# cs4272-breakout-board.net
KiCad netlist of a schematic drawn in EAGLE
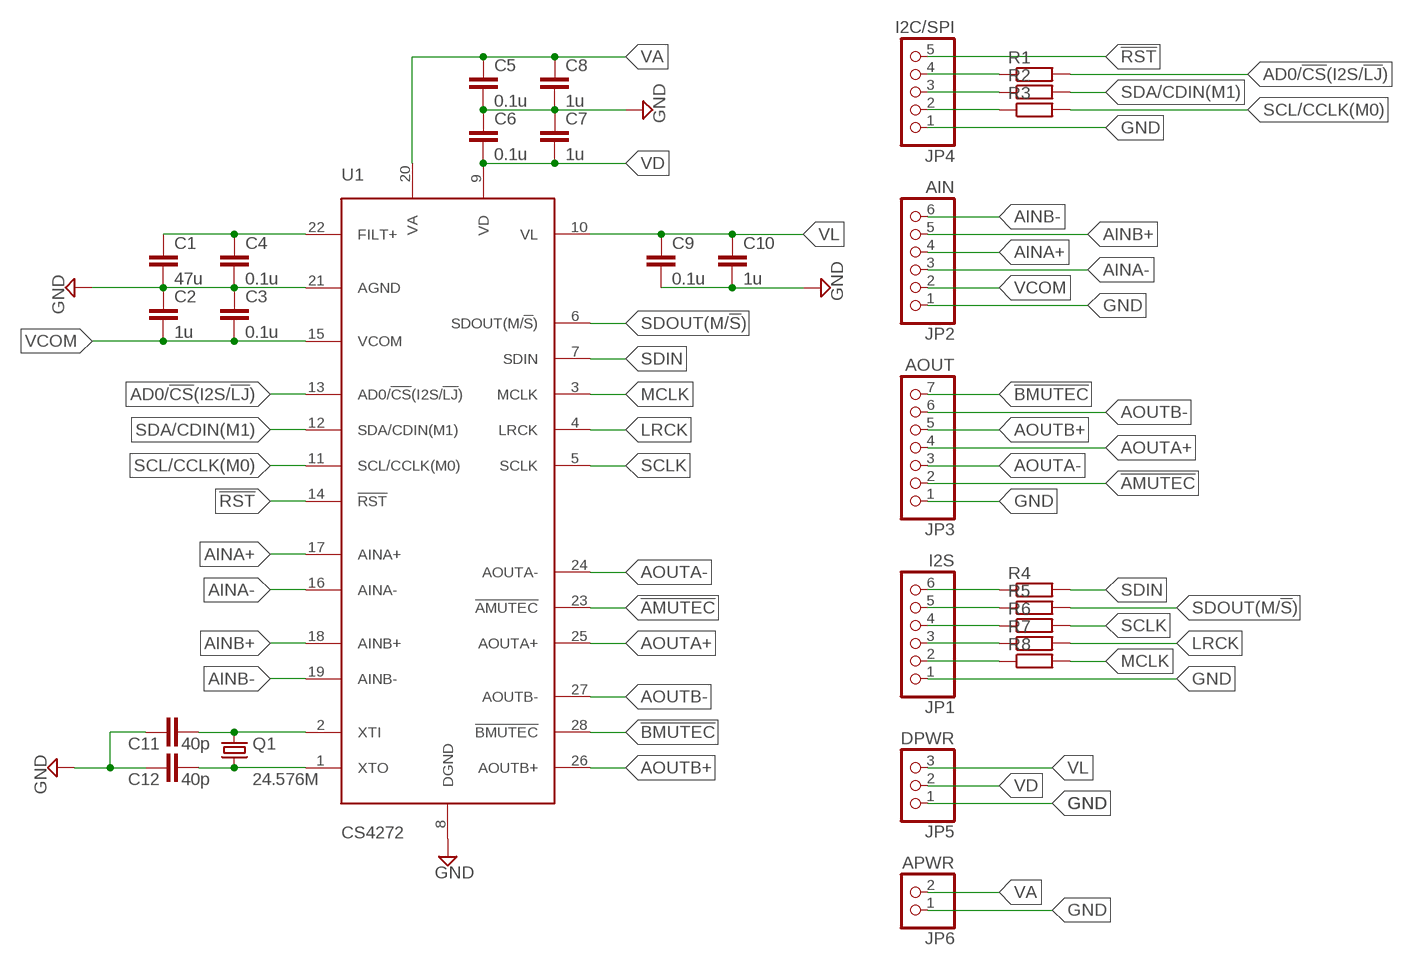
[diagram p0: schematic, sheet 1]

(export (version "E")
  (design (tool "Eeschema 10.0.6"))
  (components
    (comp (ref "C1")
      (value "47u")
      (footprint "eagle-import:C0603")
      (libsource (lib "eagle-import") (part "C-EUC0603"))
    )
    (comp (ref "C2")
      (value "1u")
      (footprint "eagle-import:C0603")
      (libsource (lib "eagle-import") (part "C-EUC0603"))
    )
    (comp (ref "C3")
      (value "0.1u")
      (footprint "eagle-import:C0603")
      (libsource (lib "eagle-import") (part "C-EUC0603"))
    )
    (comp (ref "C4")
      (value "0.1u")
      (footprint "eagle-import:C0603")
      (libsource (lib "eagle-import") (part "C-EUC0603"))
    )
    (comp (ref "C5")
      (value "0.1u")
      (footprint "eagle-import:C0603")
      (libsource (lib "eagle-import") (part "C-EUC0603"))
    )
    (comp (ref "C6")
      (value "0.1u")
      (footprint "eagle-import:C0603")
      (libsource (lib "eagle-import") (part "C-EUC0603"))
    )
    (comp (ref "C7")
      (value "1u")
      (footprint "eagle-import:C0603")
      (libsource (lib "eagle-import") (part "C-EUC0603"))
    )
    (comp (ref "C8")
      (value "1u")
      (footprint "eagle-import:C0603")
      (libsource (lib "eagle-import") (part "C-EUC0603"))
    )
    (comp (ref "C9")
      (value "0.1u")
      (footprint "eagle-import:C0603")
      (libsource (lib "eagle-import") (part "C-EUC0603"))
    )
    (comp (ref "C10")
      (value "1u")
      (footprint "eagle-import:C0603")
      (libsource (lib "eagle-import") (part "C-EUC0603"))
    )
    (comp (ref "C11")
      (value "40p")
      (footprint "eagle-import:C0603")
      (libsource (lib "eagle-import") (part "C-EUC0603"))
    )
    (comp (ref "C12")
      (value "40p")
      (footprint "eagle-import:C0603")
      (libsource (lib "eagle-import") (part "C-EUC0603"))
    )
    (comp (ref "JP1")
      (value "I2S")
      (footprint "eagle-import:1X06")
      (libsource (lib "eagle-import") (part "PINHD-1X6"))
    )
    (comp (ref "JP2")
      (value "AIN")
      (footprint "eagle-import:1X06")
      (libsource (lib "eagle-import") (part "PINHD-1X6"))
    )
    (comp (ref "JP3")
      (value "AOUT")
      (footprint "eagle-import:1X07")
      (libsource (lib "eagle-import") (part "PINHD-1X7"))
    )
    (comp (ref "JP4")
      (value "I2C/SPI")
      (footprint "eagle-import:1X05")
      (libsource (lib "eagle-import") (part "PINHD-1X5"))
    )
    (comp (ref "JP5")
      (value "DPWR")
      (footprint "eagle-import:1X03")
      (libsource (lib "eagle-import") (part "PINHD-1X3"))
    )
    (comp (ref "JP6")
      (value "APWR")
      (footprint "eagle-import:1X02")
      (libsource (lib "eagle-import") (part "PINHD-1X2"))
    )
    (comp (ref "Q1")
      (value "24.576M")
      (footprint "eagle-import:HC49_S")
      (libsource (lib "eagle-import") (part "CRYSTALHC49S"))
    )
    (comp (ref "R1")
      (value "R-EU_R0603")
      (footprint "eagle-import:R0603")
      (libsource (lib "eagle-import") (part "R-EU_R0603"))
    )
    (comp (ref "R2")
      (value "R-EU_R0603")
      (footprint "eagle-import:R0603")
      (libsource (lib "eagle-import") (part "R-EU_R0603"))
    )
    (comp (ref "R3")
      (value "R-EU_R0603")
      (footprint "eagle-import:R0603")
      (libsource (lib "eagle-import") (part "R-EU_R0603"))
    )
    (comp (ref "R4")
      (value "R-EU_R0603")
      (footprint "eagle-import:R0603")
      (libsource (lib "eagle-import") (part "R-EU_R0603"))
    )
    (comp (ref "R5")
      (value "R-EU_R0603")
      (footprint "eagle-import:R0603")
      (libsource (lib "eagle-import") (part "R-EU_R0603"))
    )
    (comp (ref "R6")
      (value "R-EU_R0603")
      (footprint "eagle-import:R0603")
      (libsource (lib "eagle-import") (part "R-EU_R0603"))
    )
    (comp (ref "R7")
      (value "R-EU_R0603")
      (footprint "eagle-import:R0603")
      (libsource (lib "eagle-import") (part "R-EU_R0603"))
    )
    (comp (ref "R8")
      (value "R-EU_R0603")
      (footprint "eagle-import:R0603")
      (libsource (lib "eagle-import") (part "R-EU_R0603"))
    )
    (comp (ref "U1")
      (value "CS4272")
      (footprint "eagle-import:SOP65P640X120-28")
      (libsource (lib "eagle-import") (part "CS4272"))
    )
  )
  (nets
    (net (code "1") (name "/AD0{slash}~{CS}(I2S{slash}~{LJ})") (class "Default")
      (node (ref "R1") (pin "2") (pinfunction "2_2") (pintype "passive"))
      (node (ref "U1") (pin "13") (pinfunction "AD0/~{CS}(I2S/~{LJ})_13") (pintype "input"))
    )
    (net (code "2") (name "/SDOUT(M{slash}~{S})") (class "Default")
      (node (ref "R5") (pin "2") (pinfunction "2_2") (pintype "passive"))
      (node (ref "U1") (pin "6") (pinfunction "SDOUT(M/~{S})_6") (pintype "output"))
    )
    (net (code "3") (name "/~{AMUTEC}") (class "Default")
      (node (ref "JP3") (pin "2") (pinfunction "2_2") (pintype "passive"))
      (node (ref "U1") (pin "23") (pinfunction "~{AMUTEC}_23") (pintype "output"))
    )
    (net (code "4") (name "/~{BMUTEC}") (class "Default")
      (node (ref "JP3") (pin "7") (pinfunction "7_7") (pintype "passive"))
      (node (ref "U1") (pin "28") (pinfunction "~{BMUTEC}_28") (pintype "output"))
    )
    (net (code "5") (name "/~{RST}") (class "Default")
      (node (ref "JP4") (pin "5") (pinfunction "5_5") (pintype "passive"))
      (node (ref "U1") (pin "14") (pinfunction "~{RST}_14") (pintype "input"))
    )
    (net (code "6") (name "AINA+") (class "Default")
      (node (ref "JP2") (pin "4") (pinfunction "4_4") (pintype "passive"))
      (node (ref "U1") (pin "17") (pinfunction "AINA+_17") (pintype "input"))
    )
    (net (code "7") (name "AINA-") (class "Default")
      (node (ref "JP2") (pin "3") (pinfunction "3_3") (pintype "passive"))
      (node (ref "U1") (pin "16") (pinfunction "AINA-_16") (pintype "input"))
    )
    (net (code "8") (name "AINB+") (class "Default")
      (node (ref "JP2") (pin "5") (pinfunction "5_5") (pintype "passive"))
      (node (ref "U1") (pin "18") (pinfunction "AINB+_18") (pintype "input"))
    )
    (net (code "9") (name "AINB-") (class "Default")
      (node (ref "JP2") (pin "6") (pinfunction "6_6") (pintype "passive"))
      (node (ref "U1") (pin "19") (pinfunction "AINB-_19") (pintype "input"))
    )
    (net (code "10") (name "AOUTA+") (class "Default")
      (node (ref "JP3") (pin "4") (pinfunction "4_4") (pintype "passive"))
      (node (ref "U1") (pin "25") (pinfunction "AOUTA+_25") (pintype "output"))
    )
    (net (code "11") (name "AOUTA-") (class "Default")
      (node (ref "JP3") (pin "3") (pinfunction "3_3") (pintype "passive"))
      (node (ref "U1") (pin "24") (pinfunction "AOUTA-_24") (pintype "output"))
    )
    (net (code "12") (name "AOUTB+") (class "Default")
      (node (ref "JP3") (pin "5") (pinfunction "5_5") (pintype "passive"))
      (node (ref "U1") (pin "26") (pinfunction "AOUTB+_26") (pintype "output"))
    )
    (net (code "13") (name "AOUTB-") (class "Default")
      (node (ref "JP3") (pin "6") (pinfunction "6_6") (pintype "passive"))
      (node (ref "U1") (pin "27") (pinfunction "AOUTB-_27") (pintype "output"))
    )
    (net (code "14") (name "GND") (class "Default")
      (node (ref "C1") (pin "2") (pinfunction "2_2") (pintype "passive"))
      (node (ref "C10") (pin "2") (pinfunction "2_2") (pintype "passive"))
      (node (ref "C11") (pin "1") (pinfunction "1_1") (pintype "passive"))
      (node (ref "C12") (pin "1") (pinfunction "1_1") (pintype "passive"))
      (node (ref "C2") (pin "1") (pinfunction "1_1") (pintype "passive"))
      (node (ref "C3") (pin "1") (pinfunction "1_1") (pintype "passive"))
      (node (ref "C4") (pin "2") (pinfunction "2_2") (pintype "passive"))
      (node (ref "C5") (pin "2") (pinfunction "2_2") (pintype "passive"))
      (node (ref "C6") (pin "1") (pinfunction "1_1") (pintype "passive"))
      (node (ref "C7") (pin "1") (pinfunction "1_1") (pintype "passive"))
      (node (ref "C8") (pin "2") (pinfunction "2_2") (pintype "passive"))
      (node (ref "C9") (pin "2") (pinfunction "2_2") (pintype "passive"))
      (node (ref "JP1") (pin "1") (pinfunction "1_1") (pintype "passive"))
      (node (ref "JP2") (pin "1") (pinfunction "1_1") (pintype "passive"))
      (node (ref "JP3") (pin "1") (pinfunction "1_1") (pintype "passive"))
      (node (ref "JP4") (pin "1") (pinfunction "1_1") (pintype "passive"))
      (node (ref "JP5") (pin "1") (pinfunction "1_1") (pintype "passive"))
      (node (ref "JP6") (pin "1") (pinfunction "1_1") (pintype "passive"))
      (node (ref "U1") (pin "21") (pinfunction "AGND_21") (pintype "bidirectional"))
      (node (ref "U1") (pin "8") (pinfunction "DGND_8") (pintype "input"))
    )
    (net (code "15") (name "LRCK") (class "Default")
      (node (ref "R7") (pin "2") (pinfunction "2_2") (pintype "passive"))
      (node (ref "U1") (pin "4") (pinfunction "LRCK_4") (pintype "bidirectional"))
    )
    (net (code "16") (name "MCLK") (class "Default")
      (node (ref "R8") (pin "2") (pinfunction "2_2") (pintype "passive"))
      (node (ref "U1") (pin "3") (pinfunction "MCLK_3") (pintype "bidirectional"))
    )
    (net (code "17") (name "Net-(JP1-Pad2)") (class "Default")
      (node (ref "JP1") (pin "2") (pinfunction "2_2") (pintype "passive"))
      (node (ref "R8") (pin "1") (pinfunction "1_1") (pintype "passive"))
    )
    (net (code "18") (name "Net-(JP1-Pad3)") (class "Default")
      (node (ref "JP1") (pin "3") (pinfunction "3_3") (pintype "passive"))
      (node (ref "R7") (pin "1") (pinfunction "1_1") (pintype "passive"))
    )
    (net (code "19") (name "Net-(JP1-Pad4)") (class "Default")
      (node (ref "JP1") (pin "4") (pinfunction "4_4") (pintype "passive"))
      (node (ref "R6") (pin "1") (pinfunction "1_1") (pintype "passive"))
    )
    (net (code "20") (name "Net-(JP1-Pad5)") (class "Default")
      (node (ref "JP1") (pin "5") (pinfunction "5_5") (pintype "passive"))
      (node (ref "R5") (pin "1") (pinfunction "1_1") (pintype "passive"))
    )
    (net (code "21") (name "Net-(JP1-Pad6)") (class "Default")
      (node (ref "JP1") (pin "6") (pinfunction "6_6") (pintype "passive"))
      (node (ref "R4") (pin "1") (pinfunction "1_1") (pintype "passive"))
    )
    (net (code "22") (name "Net-(JP4-Pad2)") (class "Default")
      (node (ref "JP4") (pin "2") (pinfunction "2_2") (pintype "passive"))
      (node (ref "R3") (pin "1") (pinfunction "1_1") (pintype "passive"))
    )
    (net (code "23") (name "Net-(JP4-Pad3)") (class "Default")
      (node (ref "JP4") (pin "3") (pinfunction "3_3") (pintype "passive"))
      (node (ref "R2") (pin "1") (pinfunction "1_1") (pintype "passive"))
    )
    (net (code "24") (name "Net-(JP4-Pad4)") (class "Default")
      (node (ref "JP4") (pin "4") (pinfunction "4_4") (pintype "passive"))
      (node (ref "R1") (pin "1") (pinfunction "1_1") (pintype "passive"))
    )
    (net (code "25") (name "Net-(U1-FILT+)") (class "Default")
      (node (ref "C1") (pin "1") (pinfunction "1_1") (pintype "passive"))
      (node (ref "C4") (pin "1") (pinfunction "1_1") (pintype "passive"))
      (node (ref "U1") (pin "22") (pinfunction "FILT+_22") (pintype "output"))
    )
    (net (code "26") (name "Net-(U1-XTI)") (class "Default")
      (node (ref "C11") (pin "2") (pinfunction "2_2") (pintype "passive"))
      (node (ref "Q1") (pin "2") (pinfunction "2_2") (pintype "passive"))
      (node (ref "U1") (pin "2") (pinfunction "XTI_2") (pintype "bidirectional"))
    )
    (net (code "27") (name "Net-(U1-XTO)") (class "Default")
      (node (ref "C12") (pin "2") (pinfunction "2_2") (pintype "passive"))
      (node (ref "Q1") (pin "1") (pinfunction "1_1") (pintype "passive"))
      (node (ref "U1") (pin "1") (pinfunction "XTO_1") (pintype "bidirectional"))
    )
    (net (code "28") (name "SCLK") (class "Default")
      (node (ref "R6") (pin "2") (pinfunction "2_2") (pintype "passive"))
      (node (ref "U1") (pin "5") (pinfunction "SCLK_5") (pintype "bidirectional"))
    )
    (net (code "29") (name "SCL{slash}CCLK(M0)") (class "Default")
      (node (ref "R3") (pin "2") (pinfunction "2_2") (pintype "passive"))
      (node (ref "U1") (pin "11") (pinfunction "SCL/CCLK(M0)_11") (pintype "input"))
    )
    (net (code "30") (name "SDA{slash}CDIN(M1)") (class "Default")
      (node (ref "R2") (pin "2") (pinfunction "2_2") (pintype "passive"))
      (node (ref "U1") (pin "12") (pinfunction "SDA/CDIN(M1)_12") (pintype "bidirectional"))
    )
    (net (code "31") (name "SDIN") (class "Default")
      (node (ref "R4") (pin "2") (pinfunction "2_2") (pintype "passive"))
      (node (ref "U1") (pin "7") (pinfunction "SDIN_7") (pintype "input"))
    )
    (net (code "32") (name "VA") (class "Default")
      (node (ref "C5") (pin "1") (pinfunction "1_1") (pintype "passive"))
      (node (ref "C8") (pin "1") (pinfunction "1_1") (pintype "passive"))
      (node (ref "JP6") (pin "2") (pinfunction "2_2") (pintype "passive"))
      (node (ref "U1") (pin "20") (pinfunction "VA_20") (pintype "input"))
    )
    (net (code "33") (name "VCOM") (class "Default")
      (node (ref "C2") (pin "2") (pinfunction "2_2") (pintype "passive"))
      (node (ref "C3") (pin "2") (pinfunction "2_2") (pintype "passive"))
      (node (ref "JP2") (pin "2") (pinfunction "2_2") (pintype "passive"))
      (node (ref "U1") (pin "15") (pinfunction "VCOM_15") (pintype "output"))
    )
    (net (code "34") (name "VD") (class "Default")
      (node (ref "C6") (pin "2") (pinfunction "2_2") (pintype "passive"))
      (node (ref "C7") (pin "2") (pinfunction "2_2") (pintype "passive"))
      (node (ref "JP5") (pin "2") (pinfunction "2_2") (pintype "passive"))
      (node (ref "U1") (pin "9") (pinfunction "VD_9") (pintype "input"))
    )
    (net (code "35") (name "VL") (class "Default")
      (node (ref "C10") (pin "1") (pinfunction "1_1") (pintype "passive"))
      (node (ref "C9") (pin "1") (pinfunction "1_1") (pintype "passive"))
      (node (ref "JP5") (pin "3") (pinfunction "3_3") (pintype "passive"))
      (node (ref "U1") (pin "10") (pinfunction "VL_10") (pintype "input"))
    )
  )
)
